# SPI_IFC.net
KiCad netlist of a schematic drawn in Altium Designer
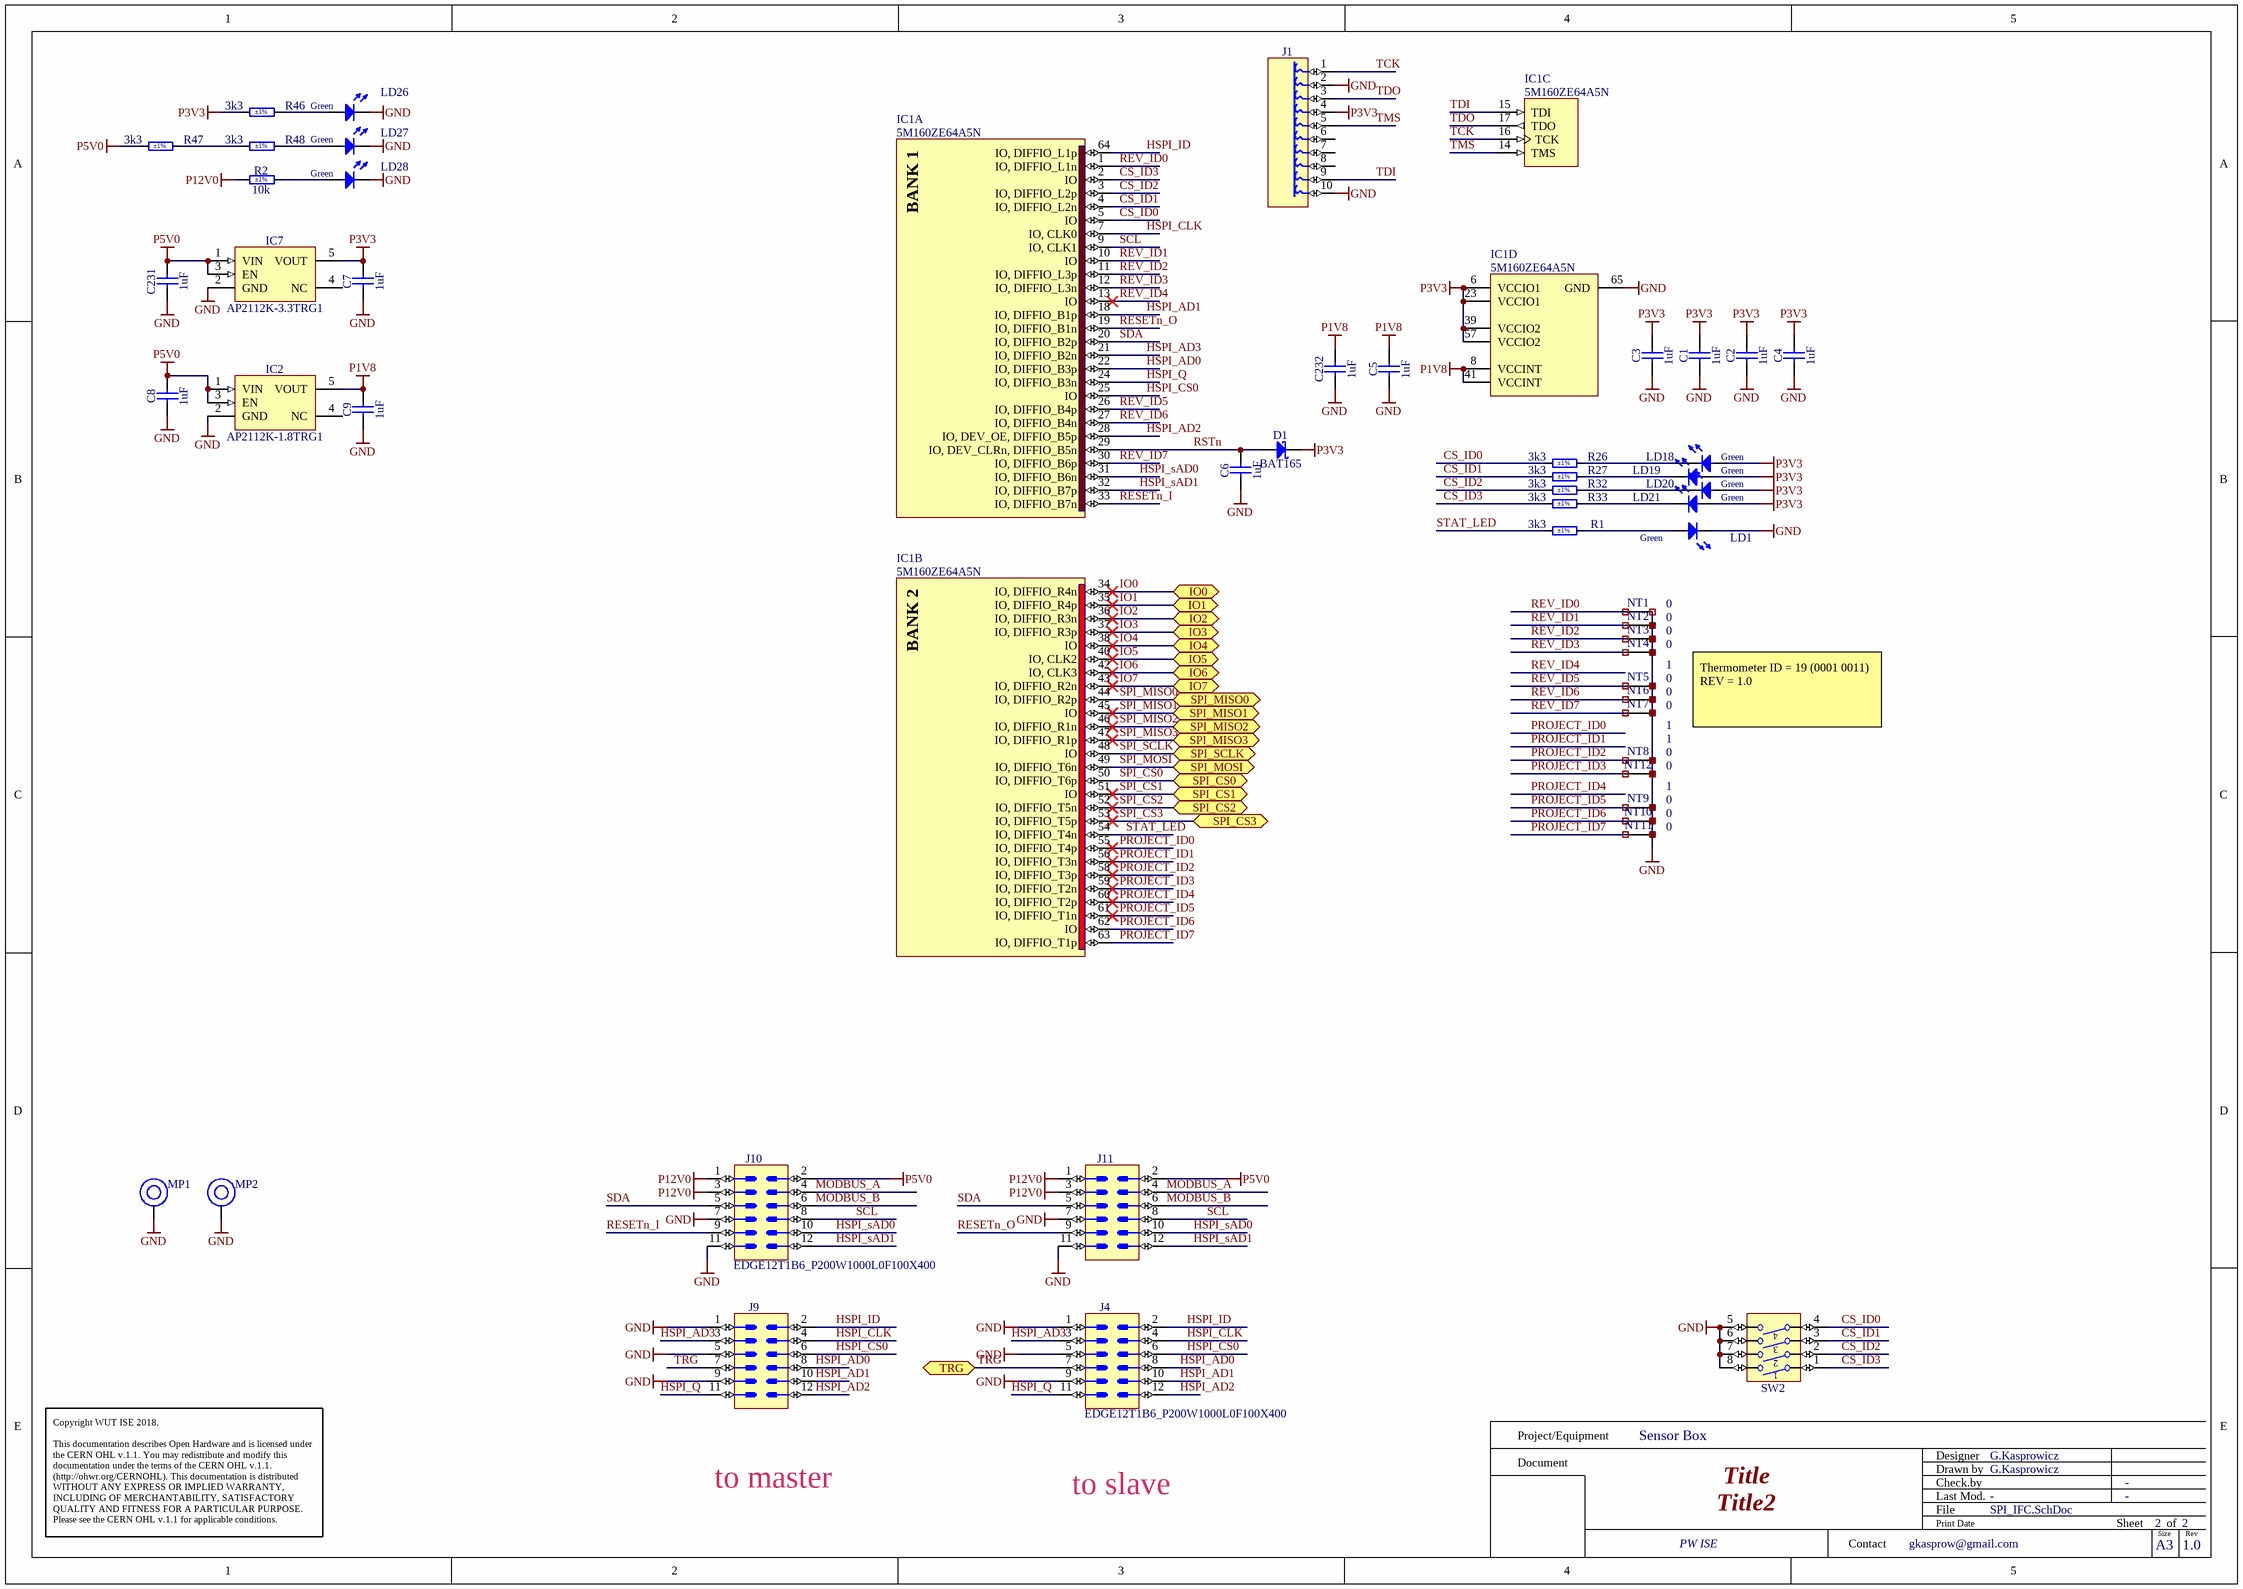
[diagram p0: SPI_IFC.SchDoc]

(export (version "E")
  (design (tool "Eeschema 10.0.6"))
  (components
    (comp (ref "C1")
      (value "1uF")
      (footprint "CAPC1005X55N")
      (description "Non-polarised capacitor")
      (fields
        (field (name "PART NUMBER") "CC0402_1UF_16V_10%_X5R")
        (field (name "VOLTAGE") "16V")
        (field (name "AUTHOR") "CERN DEM JLC")
      )
      (libsource (lib "Capacitors") (part "Capacitor - non polarized"))
    )
    (comp (ref "C2")
      (value "1uF")
      (footprint "CAPC1005X55N")
      (description "Non-polarised capacitor")
      (fields
        (field (name "PART NUMBER") "CC0402_1UF_16V_10%_X5R")
        (field (name "VOLTAGE") "16V")
        (field (name "AUTHOR") "CERN DEM JLC")
      )
      (libsource (lib "Capacitors") (part "Capacitor - non polarized"))
    )
    (comp (ref "C3")
      (value "1uF")
      (footprint "CAPC1005X55N")
      (description "Non-polarised capacitor")
      (fields
        (field (name "PART NUMBER") "CC0402_1UF_16V_10%_X5R")
        (field (name "VOLTAGE") "16V")
        (field (name "AUTHOR") "CERN DEM JLC")
      )
      (libsource (lib "Capacitors") (part "Capacitor - non polarized"))
    )
    (comp (ref "C4")
      (value "1uF")
      (footprint "CAPC1005X55N")
      (description "Non-polarised capacitor")
      (fields
        (field (name "PART NUMBER") "CC0402_1UF_16V_10%_X5R")
        (field (name "VOLTAGE") "16V")
        (field (name "AUTHOR") "CERN DEM JLC")
      )
      (libsource (lib "Capacitors") (part "Capacitor - non polarized"))
    )
    (comp (ref "C5")
      (value "1uF")
      (footprint "CAPC1005X55N")
      (description "Non-polarised capacitor")
      (fields
        (field (name "PART NUMBER") "CC0402_1UF_16V_10%_X5R")
        (field (name "VOLTAGE") "16V")
        (field (name "AUTHOR") "CERN DEM JLC")
      )
      (libsource (lib "Capacitors") (part "Capacitor - non polarized"))
    )
    (comp (ref "C6")
      (value "1uF")
      (footprint "CAPC1005X55N")
      (description "Non-polarised capacitor")
      (fields
        (field (name "PART NUMBER") "CC0402_1UF_16V_10%_X5R")
        (field (name "VOLTAGE") "16V")
        (field (name "AUTHOR") "CERN DEM JLC")
      )
      (libsource (lib "Capacitors") (part "Capacitor - non polarized"))
    )
    (comp (ref "C7")
      (value "1uF")
      (footprint "CAPC1005X55N")
      (description "Non-polarised capacitor")
      (fields
        (field (name "PART NUMBER") "CC0402_1UF_16V_10%_X5R")
        (field (name "VOLTAGE") "16V")
        (field (name "AUTHOR") "CERN DEM JLC")
      )
      (libsource (lib "Capacitors") (part "Capacitor - non polarized"))
    )
    (comp (ref "C8")
      (value "1uF")
      (footprint "CAPC1005X55N")
      (description "Non-polarised capacitor")
      (fields
        (field (name "PART NUMBER") "CC0402_1UF_16V_10%_X5R")
        (field (name "VOLTAGE") "16V")
        (field (name "AUTHOR") "CERN DEM JLC")
      )
      (libsource (lib "Capacitors") (part "Capacitor - non polarized"))
    )
    (comp (ref "C9")
      (value "1uF")
      (footprint "CAPC1005X55N")
      (description "Non-polarised capacitor")
      (fields
        (field (name "PART NUMBER") "CC0402_1UF_16V_10%_X5R")
        (field (name "VOLTAGE") "16V")
        (field (name "AUTHOR") "CERN DEM JLC")
      )
      (libsource (lib "Capacitors") (part "Capacitor - non polarized"))
    )
    (comp (ref "C231")
      (value "1uF")
      (footprint "CAPC1005X55N")
      (description "Non-polarised capacitor")
      (fields
        (field (name "PART NUMBER") "CC0402_1UF_16V_10%_X5R")
        (field (name "VOLTAGE") "16V")
        (field (name "AUTHOR") "CERN DEM JLC")
      )
      (libsource (lib "Capacitors") (part "Capacitor - non polarized"))
    )
    (comp (ref "C232")
      (value "1uF")
      (footprint "CAPC1005X55N")
      (description "Non-polarised capacitor")
      (fields
        (field (name "PART NUMBER") "CC0402_1UF_16V_10%_X5R")
        (field (name "VOLTAGE") "16V")
        (field (name "AUTHOR") "CERN DEM JLC")
      )
      (libsource (lib "Capacitors") (part "Capacitor - non polarized"))
    )
    (comp (ref "D1")
      (value "BAT165")
      (footprint "SOD2512X110N")
      (description "Schottky Diode")
      (fields
        (field (name "VOLTAGE") "40V")
        (field (name "POWER") "750mA")
        (field (name "AUTHOR") "CERN DEM JLC")
      )
      (libsource (lib "ICs And Semiconductors") (part "Diode Schottky"))
    )
    (comp (ref "IC1")
      (value "5M160ZE64A5N")
      (footprint "QFP40P900X900X120-65N-S550")
      (fields (field (name "MANUFACTURER") "ALTERA") (field (name "AUTHOR") "CERN DEM JLC"))
      (libsource (lib "ICs And Semiconductors") (part "5M160ZE64A5N"))
    )
    (comp (ref "IC2")
      (value "AP2112K-1.8TRG1")
      (footprint "SOT95P285X140-5N")
      (description "600mA CMOS Low Dropout Linear Regulator with Enable")
      (fields
        (field (name "MANUFACTURER") "DIODES INCORPORATED")
        (field (name "MANUFACTURER PART NUMBER") "AP2112K-1.8")
        (field (name "AUTHOR") "CERN DEM JLC")
      )
      (libsource (lib "ICs And Semiconductors") (part "AP2112K"))
    )
    (comp (ref "IC7")
      (value "AP2112K-3.3TRG1")
      (footprint "SOT95P285X140-5N")
      (description "600mA CMOS Low Dropout Linear Regulator with Enable")
      (fields
        (field (name "MANUFACTURER") "DIODES INCORPORATED")
        (field (name "MANUFACTURER PART NUMBER") "AP2112K-3.3")
        (field (name "AUTHOR") "CERN DEM MR")
      )
      (libsource (lib "ICs And Semiconductors") (part "AP2112K"))
    )
    (comp (ref "J1")
      (value "TC2050-IDC")
      (footprint "TC2050-IDC")
      (description "TC2030-MCP and TC2050-IDC Pad Contact")
      (fields (field (name "AUTHOR") "CERN DEM HF"))
      (libsource (lib "Eletro-mechanical") (part "TC2050-IDC"))
    )
    (comp (ref "J4")
      (value "~")
      (footprint "EDGE12T1B6_P200W1000L0F100X400")
      (description "PCB Edge Connector 12 (2x6)")
      (fields
        (field (name "PART NUMBER") "EDGE10T1B6_P200W1000L0F100X400")
        (field (name "AUTHOR") "CERN DEM MR")
      )
      (libsource (lib "Connectors") (part "PCB Edge Connector 12 (2x6)"))
    )
    (comp (ref "J9")
      (value "~")
      (footprint "EDGE12T5B10_P200W1000L0F100X400")
      (description "PCB Edge Connector 12 (2x6)")
      (fields (field (name "PART NUMBER") "EDGE12T5B10_P200W1000L0F100X400") (field (name "AUTHOR") "GK"))
      (libsource (lib "Connectors") (part "PCB Edge Connector 12 (2x6) R"))
    )
    (comp (ref "J10")
      (value "~")
      (footprint "EDGE12T1B6_P200W1000L0F100X400")
      (description "PCB Edge Connector 12 (2x6)")
      (fields
        (field (name "PART NUMBER") "EDGE10T1B6_P200W1000L0F100X400")
        (field (name "AUTHOR") "CERN DEM MR")
      )
      (libsource (lib "Connectors") (part "PCB Edge Connector 12 (2x6)"))
    )
    (comp (ref "J11")
      (value "~")
      (footprint "EDGE12T5B10_P200W1000L0F100X400")
      (description "PCB Edge Connector 12 (2x6)")
      (fields (field (name "PART NUMBER") "EDGE12T5B10_P200W1000L0F100X400") (field (name "AUTHOR") "GK"))
      (libsource (lib "Connectors") (part "PCB Edge Connector 12 (2x6) R"))
    )
    (comp (ref "LD1")
      (value "Green")
      (footprint "LED_KINGBRIGHT_KP-1608CGCK")
      (description "LED Green 1C 2A")
      (fields
        (field (name "PART NUMBER") "LED_KINGBRIGHT_KP-1608CGCK")
        (field (name "MANUFACTURER") "KINGBRIGHT")
        (field (name "AUTHOR") "CERN DEM HF")
      )
      (libsource (lib "ICs And Semiconductors") (part "LED Green 1C 2A"))
    )
    (comp (ref "LD18")
      (value "Green")
      (footprint "LED_KINGBRIGHT_KP-1608CGCK")
      (description "LED Green 1C 2A")
      (fields
        (field (name "PART NUMBER") "LED_KINGBRIGHT_KP-1608CGCK")
        (field (name "MANUFACTURER") "KINGBRIGHT")
        (field (name "AUTHOR") "CERN DEM HF")
      )
      (libsource (lib "ICs And Semiconductors") (part "LED Green 1C 2A"))
    )
    (comp (ref "LD19")
      (value "Green")
      (footprint "LED_KINGBRIGHT_KP-1608CGCK")
      (description "LED Green 1C 2A")
      (fields
        (field (name "PART NUMBER") "LED_KINGBRIGHT_KP-1608CGCK")
        (field (name "MANUFACTURER") "KINGBRIGHT")
        (field (name "AUTHOR") "CERN DEM HF")
      )
      (libsource (lib "ICs And Semiconductors") (part "LED Green 1C 2A"))
    )
    (comp (ref "LD20")
      (value "Green")
      (footprint "LED_KINGBRIGHT_KP-1608CGCK")
      (description "LED Green 1C 2A")
      (fields
        (field (name "PART NUMBER") "LED_KINGBRIGHT_KP-1608CGCK")
        (field (name "MANUFACTURER") "KINGBRIGHT")
        (field (name "AUTHOR") "CERN DEM HF")
      )
      (libsource (lib "ICs And Semiconductors") (part "LED Green 1C 2A"))
    )
    (comp (ref "LD21")
      (value "Green")
      (footprint "LED_KINGBRIGHT_KP-1608CGCK")
      (description "LED Green 1C 2A")
      (fields
        (field (name "PART NUMBER") "LED_KINGBRIGHT_KP-1608CGCK")
        (field (name "MANUFACTURER") "KINGBRIGHT")
        (field (name "AUTHOR") "CERN DEM HF")
      )
      (libsource (lib "ICs And Semiconductors") (part "LED Green 1C 2A"))
    )
    (comp (ref "LD26")
      (value "Green")
      (footprint "LED_KINGBRIGHT_KP-1608CGCK")
      (description "LED Green 1C 2A")
      (fields
        (field (name "PART NUMBER") "LED_KINGBRIGHT_KP-1608CGCK")
        (field (name "MANUFACTURER") "KINGBRIGHT")
        (field (name "AUTHOR") "CERN DEM HF")
      )
      (libsource (lib "ICs And Semiconductors") (part "LED Green 1C 2A"))
    )
    (comp (ref "LD27")
      (value "Green")
      (footprint "LED_KINGBRIGHT_KP-1608CGCK")
      (description "LED Green 1C 2A")
      (fields
        (field (name "PART NUMBER") "LED_KINGBRIGHT_KP-1608CGCK")
        (field (name "MANUFACTURER") "KINGBRIGHT")
        (field (name "AUTHOR") "CERN DEM HF")
      )
      (libsource (lib "ICs And Semiconductors") (part "LED Green 1C 2A"))
    )
    (comp (ref "LD28")
      (value "Green")
      (footprint "LED_KINGBRIGHT_KP-1608CGCK")
      (description "LED Green 1C 2A")
      (fields
        (field (name "PART NUMBER") "LED_KINGBRIGHT_KP-1608CGCK")
        (field (name "MANUFACTURER") "KINGBRIGHT")
        (field (name "AUTHOR") "CERN DEM HF")
      )
      (libsource (lib "ICs And Semiconductors") (part "LED Green 1C 2A"))
    )
    (comp (ref "MP1")
      (value "M1.6 x 3mm")
      (footprint "97730306330")
      (description "WA-SMSI SMT Steel Spacer with internal Thread Bottom closed, OD 3.3mm, M1.6 x 3mm")
      (fields
        (field (name "MANUFACTURER PART NUMBER") "97730306330R")
        (field (name "MANUFACTURER") "Wurth Elektronik")
      )
      (libsource (lib "Altium_WA-SMSI (rev22a)") (part "97730306330R"))
    )
    (comp (ref "MP2")
      (value "M1.6 x 3mm")
      (footprint "97730306330")
      (description "WA-SMSI SMT Steel Spacer with internal Thread Bottom closed, OD 3.3mm, M1.6 x 3mm")
      (fields
        (field (name "MANUFACTURER PART NUMBER") "97730306330R")
        (field (name "MANUFACTURER") "Wurth Elektronik")
      )
      (libsource (lib "Altium_WA-SMSI (rev22a)") (part "97730306330R"))
    )
    (comp (ref "NT1")
      (value "Net Tie")
      (footprint "Net Tie 3")
      (fields (field (name "PART NUMBER") "Net Tie 3") (field (name "AUTHOR") "CERN DEM HF"))
      (libsource (lib "Eletro-mechanical") (part "Net Tie_a"))
    )
    (comp (ref "NT2")
      (value "Net Tie")
      (footprint "Net Tie 3")
      (fields (field (name "PART NUMBER") "Net Tie 3") (field (name "AUTHOR") "CERN DEM HF"))
      (libsource (lib "Eletro-mechanical") (part "Net Tie_a"))
    )
    (comp (ref "NT3")
      (value "Net Tie")
      (footprint "Net Tie 3")
      (fields (field (name "PART NUMBER") "Net Tie 3") (field (name "AUTHOR") "CERN DEM HF"))
      (libsource (lib "Eletro-mechanical") (part "Net Tie_a"))
    )
    (comp (ref "NT4")
      (value "Net Tie")
      (footprint "Net Tie 3")
      (fields (field (name "PART NUMBER") "Net Tie 3") (field (name "AUTHOR") "CERN DEM HF"))
      (libsource (lib "Eletro-mechanical") (part "Net Tie_a"))
    )
    (comp (ref "NT5")
      (value "Net Tie")
      (footprint "Net Tie 3")
      (fields (field (name "PART NUMBER") "Net Tie 3") (field (name "AUTHOR") "CERN DEM HF"))
      (libsource (lib "Eletro-mechanical") (part "Net Tie_a"))
    )
    (comp (ref "NT6")
      (value "Net Tie")
      (footprint "Net Tie 3")
      (fields (field (name "PART NUMBER") "Net Tie 3") (field (name "AUTHOR") "CERN DEM HF"))
      (libsource (lib "Eletro-mechanical") (part "Net Tie_a"))
    )
    (comp (ref "NT7")
      (value "Net Tie")
      (footprint "Net Tie 3")
      (fields (field (name "PART NUMBER") "Net Tie 3") (field (name "AUTHOR") "CERN DEM HF"))
      (libsource (lib "Eletro-mechanical") (part "Net Tie_a"))
    )
    (comp (ref "NT8")
      (value "Net Tie")
      (footprint "Net Tie 3")
      (fields (field (name "PART NUMBER") "Net Tie 3") (field (name "AUTHOR") "CERN DEM HF"))
      (libsource (lib "Eletro-mechanical") (part "Net Tie_a"))
    )
    (comp (ref "NT9")
      (value "Net Tie")
      (footprint "Net Tie 3")
      (fields (field (name "PART NUMBER") "Net Tie 3") (field (name "AUTHOR") "CERN DEM HF"))
      (libsource (lib "Eletro-mechanical") (part "Net Tie_a"))
    )
    (comp (ref "NT10")
      (value "Net Tie")
      (footprint "Net Tie 3")
      (fields (field (name "PART NUMBER") "Net Tie 3") (field (name "AUTHOR") "CERN DEM HF"))
      (libsource (lib "Eletro-mechanical") (part "Net Tie_a"))
    )
    (comp (ref "NT11")
      (value "Net Tie")
      (footprint "Net Tie 3")
      (fields (field (name "PART NUMBER") "Net Tie 3") (field (name "AUTHOR") "CERN DEM HF"))
      (libsource (lib "Eletro-mechanical") (part "Net Tie_a"))
    )
    (comp (ref "NT12")
      (value "Net Tie")
      (footprint "Net Tie 3")
      (fields (field (name "PART NUMBER") "Net Tie 3") (field (name "AUTHOR") "CERN DEM HF"))
      (libsource (lib "Eletro-mechanical") (part "Net Tie_a"))
    )
    (comp (ref "R1")
      (value "3k3")
      (footprint "RESC1005X40N")
      (description "Resistor - 1%")
      (fields
        (field (name "TOLERANCE") "±1%")
        (field (name "PART NUMBER") "R0402_3K3_1%_0.0625W_100PPM")
        (field (name "POWER") "0.0625W")
        (field (name "AUTHOR") "CERN DEM JLC")
      )
      (libsource (lib "Resistors") (part "Resistor - 1%"))
    )
    (comp (ref "R2")
      (value "10k")
      (footprint "RESC1005X40N")
      (description "Resistor - 1%")
      (fields
        (field (name "TOLERANCE") "±1%")
        (field (name "PART NUMBER") "R0402_10K_1%_0.0625W_100PPM")
        (field (name "POWER") "0.0625W")
        (field (name "AUTHOR") "CERN DEM JLC")
      )
      (libsource (lib "Resistors") (part "Resistor - 1%"))
    )
    (comp (ref "R26")
      (value "3k3")
      (footprint "RESC1005X40N")
      (description "Resistor - 1%")
      (fields
        (field (name "TOLERANCE") "±1%")
        (field (name "PART NUMBER") "R0402_3K3_1%_0.0625W_100PPM")
        (field (name "POWER") "0.0625W")
        (field (name "AUTHOR") "CERN DEM JLC")
      )
      (libsource (lib "Resistors") (part "Resistor - 1%"))
    )
    (comp (ref "R27")
      (value "3k3")
      (footprint "RESC1005X40N")
      (description "Resistor - 1%")
      (fields
        (field (name "TOLERANCE") "±1%")
        (field (name "PART NUMBER") "R0402_3K3_1%_0.0625W_100PPM")
        (field (name "POWER") "0.0625W")
        (field (name "AUTHOR") "CERN DEM JLC")
      )
      (libsource (lib "Resistors") (part "Resistor - 1%"))
    )
    (comp (ref "R32")
      (value "3k3")
      (footprint "RESC1005X40N")
      (description "Resistor - 1%")
      (fields
        (field (name "TOLERANCE") "±1%")
        (field (name "PART NUMBER") "R0402_3K3_1%_0.0625W_100PPM")
        (field (name "POWER") "0.0625W")
        (field (name "AUTHOR") "CERN DEM JLC")
      )
      (libsource (lib "Resistors") (part "Resistor - 1%"))
    )
    (comp (ref "R33")
      (value "3k3")
      (footprint "RESC1005X40N")
      (description "Resistor - 1%")
      (fields
        (field (name "TOLERANCE") "±1%")
        (field (name "PART NUMBER") "R0402_3K3_1%_0.0625W_100PPM")
        (field (name "POWER") "0.0625W")
        (field (name "AUTHOR") "CERN DEM JLC")
      )
      (libsource (lib "Resistors") (part "Resistor - 1%"))
    )
    (comp (ref "R46")
      (value "3k3")
      (footprint "RESC1005X40N")
      (description "Resistor - 1%")
      (fields
        (field (name "TOLERANCE") "±1%")
        (field (name "PART NUMBER") "R0402_3K3_1%_0.0625W_100PPM")
        (field (name "POWER") "0.0625W")
        (field (name "AUTHOR") "CERN DEM JLC")
      )
      (libsource (lib "Resistors") (part "Resistor - 1%"))
    )
    (comp (ref "R47")
      (value "3k3")
      (footprint "RESC1005X40N")
      (description "Resistor - 1%")
      (fields
        (field (name "TOLERANCE") "±1%")
        (field (name "PART NUMBER") "R0402_3K3_1%_0.0625W_100PPM")
        (field (name "POWER") "0.0625W")
        (field (name "AUTHOR") "CERN DEM JLC")
      )
      (libsource (lib "Resistors") (part "Resistor - 1%"))
    )
    (comp (ref "R48")
      (value "3k3")
      (footprint "RESC1005X40N")
      (description "Resistor - 1%")
      (fields
        (field (name "TOLERANCE") "±1%")
        (field (name "PART NUMBER") "R0402_3K3_1%_0.0625W_100PPM")
        (field (name "POWER") "0.0625W")
        (field (name "AUTHOR") "CERN DEM JLC")
      )
      (libsource (lib "Resistors") (part "Resistor - 1%"))
    )
    (comp (ref "SW2")
      (value "Switch")
      (footprint "SW_OMRON_A6H-4102")
      (description "4 Ways SPST DIP Switch")
      (fields
        (field (name "PART NUMBER") "SW_OMRON_A6H-4102")
        (field (name "MANUFACTURER") "OMRON")
        (field (name "AUTHOR") "CERN DEM JLC")
      )
      (libsource (lib "Eletro-mechanical") (part "SW 4x SPST DIP Switch"))
    )
  )
  (nets
    (net (code "1") (name "/CS_ID0") (class "Default")
      (node (ref "IC1") (pin "5") (pinfunction "IO_5") (pintype "bidirectional"))
      (node (ref "R26") (pin "2") (pinfunction "2_2") (pintype "passive"))
      (node (ref "SW2") (pin "4") (pinfunction "4_4") (pintype "bidirectional"))
    )
    (net (code "2") (name "/CS_ID1") (class "Default")
      (node (ref "IC1") (pin "4") (pinfunction "IO,_DIFFIO_L2n_4") (pintype "bidirectional"))
      (node (ref "R27") (pin "2") (pinfunction "2_2") (pintype "passive"))
      (node (ref "SW2") (pin "3") (pinfunction "3_3") (pintype "bidirectional"))
    )
    (net (code "3") (name "/CS_ID2") (class "Default")
      (node (ref "IC1") (pin "3") (pinfunction "IO,_DIFFIO_L2p_3") (pintype "bidirectional"))
      (node (ref "R32") (pin "2") (pinfunction "2_2") (pintype "passive"))
      (node (ref "SW2") (pin "2") (pinfunction "2_2") (pintype "bidirectional"))
    )
    (net (code "4") (name "/CS_ID3") (class "Default")
      (node (ref "IC1") (pin "2") (pinfunction "IO_2") (pintype "bidirectional"))
      (node (ref "R33") (pin "2") (pinfunction "2_2") (pintype "passive"))
      (node (ref "SW2") (pin "1") (pinfunction "1_1") (pintype "bidirectional"))
    )
    (net (code "5") (name "/HSPI_AD0") (class "Default")
      (node (ref "IC1") (pin "22") (pinfunction "IO,_DIFFIO_B3p_22") (pintype "bidirectional"))
      (node (ref "J4") (pin "8") (pinfunction "8_8") (pintype "bidirectional"))
      (node (ref "J9") (pin "8") (pinfunction "8_8") (pintype "bidirectional"))
    )
    (net (code "6") (name "/HSPI_AD1") (class "Default")
      (node (ref "IC1") (pin "18") (pinfunction "IO,_DIFFIO_B1p_18") (pintype "bidirectional"))
      (node (ref "J4") (pin "10") (pinfunction "10_10") (pintype "bidirectional"))
      (node (ref "J9") (pin "10") (pinfunction "10_10") (pintype "bidirectional"))
    )
    (net (code "7") (name "/HSPI_AD2") (class "Default")
      (node (ref "IC1") (pin "28") (pinfunction "IO,_DEV_OE,_DIFFIO_B5p_28") (pintype "bidirectional"))
      (node (ref "J4") (pin "12") (pinfunction "12_12") (pintype "bidirectional"))
      (node (ref "J9") (pin "12") (pinfunction "12_12") (pintype "bidirectional"))
    )
    (net (code "8") (name "/HSPI_AD3") (class "Default")
      (node (ref "IC1") (pin "21") (pinfunction "IO,_DIFFIO_B2n_21") (pintype "bidirectional"))
      (node (ref "J4") (pin "3") (pinfunction "3_3") (pintype "bidirectional"))
      (node (ref "J9") (pin "3") (pinfunction "3_3") (pintype "bidirectional"))
    )
    (net (code "9") (name "/HSPI_CLK") (class "Default")
      (node (ref "IC1") (pin "7") (pinfunction "IO,_CLK0_7") (pintype "bidirectional"))
      (node (ref "J4") (pin "4") (pinfunction "4_4") (pintype "bidirectional"))
      (node (ref "J9") (pin "4") (pinfunction "4_4") (pintype "bidirectional"))
    )
    (net (code "10") (name "/HSPI_CS0") (class "Default")
      (node (ref "IC1") (pin "25") (pinfunction "IO_25") (pintype "bidirectional"))
      (node (ref "J4") (pin "6") (pinfunction "6_6") (pintype "bidirectional"))
      (node (ref "J9") (pin "6") (pinfunction "6_6") (pintype "bidirectional"))
    )
    (net (code "11") (name "/HSPI_ID") (class "Default")
      (node (ref "IC1") (pin "64") (pinfunction "IO,_DIFFIO_L1p_64") (pintype "bidirectional"))
      (node (ref "J4") (pin "2") (pinfunction "2_2") (pintype "bidirectional"))
      (node (ref "J9") (pin "2") (pinfunction "2_2") (pintype "bidirectional"))
    )
    (net (code "12") (name "/HSPI_Q") (class "Default")
      (node (ref "IC1") (pin "24") (pinfunction "IO,_DIFFIO_B3n_24") (pintype "bidirectional"))
      (node (ref "J4") (pin "11") (pinfunction "11_11") (pintype "bidirectional"))
      (node (ref "J9") (pin "11") (pinfunction "11_11") (pintype "bidirectional"))
    )
    (net (code "13") (name "/HSPI_sAD0") (class "Default")
      (node (ref "IC1") (pin "31") (pinfunction "IO,_DIFFIO_B6n_31") (pintype "bidirectional"))
      (node (ref "J10") (pin "10") (pinfunction "10_10") (pintype "bidirectional"))
      (node (ref "J11") (pin "10") (pinfunction "10_10") (pintype "bidirectional"))
    )
    (net (code "14") (name "/HSPI_sAD1") (class "Default")
      (node (ref "IC1") (pin "32") (pinfunction "IO,_DIFFIO_B7p_32") (pintype "bidirectional"))
      (node (ref "J10") (pin "12") (pinfunction "12_12") (pintype "bidirectional"))
      (node (ref "J11") (pin "12") (pinfunction "12_12") (pintype "bidirectional"))
    )
    (net (code "15") (name "/IO0") (class "Default")
      (node (ref "IC1") (pin "34") (pinfunction "IO,_DIFFIO_R4n_34") (pintype "bidirectional+no_connect"))
    )
    (net (code "16") (name "/IO1") (class "Default")
      (node (ref "IC1") (pin "35") (pinfunction "IO,_DIFFIO_R4p_35") (pintype "bidirectional+no_connect"))
    )
    (net (code "17") (name "/IO2") (class "Default")
      (node (ref "IC1") (pin "36") (pinfunction "IO,_DIFFIO_R3n_36") (pintype "bidirectional+no_connect"))
    )
    (net (code "18") (name "/IO3") (class "Default")
      (node (ref "IC1") (pin "37") (pinfunction "IO,_DIFFIO_R3p_37") (pintype "bidirectional+no_connect"))
    )
    (net (code "19") (name "/IO4") (class "Default")
      (node (ref "IC1") (pin "38") (pinfunction "IO_38") (pintype "bidirectional+no_connect"))
    )
    (net (code "20") (name "/IO5") (class "Default")
      (node (ref "IC1") (pin "40") (pinfunction "IO,_CLK2_40") (pintype "bidirectional+no_connect"))
    )
    (net (code "21") (name "/IO6") (class "Default")
      (node (ref "IC1") (pin "42") (pinfunction "IO,_CLK3_42") (pintype "bidirectional+no_connect"))
    )
    (net (code "22") (name "/IO7") (class "Default")
      (node (ref "IC1") (pin "43") (pinfunction "IO,_DIFFIO_R2n_43") (pintype "bidirectional+no_connect"))
    )
    (net (code "23") (name "/MODBUS_A") (class "Default")
      (node (ref "J10") (pin "4") (pinfunction "4_4") (pintype "bidirectional"))
      (node (ref "J11") (pin "4") (pinfunction "4_4") (pintype "bidirectional"))
    )
    (net (code "24") (name "/MODBUS_B") (class "Default")
      (node (ref "J10") (pin "6") (pinfunction "6_6") (pintype "bidirectional"))
      (node (ref "J11") (pin "6") (pinfunction "6_6") (pintype "bidirectional"))
    )
    (net (code "25") (name "/PROJECT_ID0") (class "Default")
      (node (ref "IC1") (pin "55") (pinfunction "IO,_DIFFIO_T4p_55") (pintype "bidirectional"))
    )
    (net (code "26") (name "/PROJECT_ID1") (class "Default")
      (node (ref "IC1") (pin "56") (pinfunction "IO,_DIFFIO_T3n_56") (pintype "bidirectional"))
    )
    (net (code "27") (name "/PROJECT_ID2") (class "Default")
      (node (ref "IC1") (pin "58") (pinfunction "IO,_DIFFIO_T3p_58") (pintype "bidirectional"))
      (node (ref "NT8") (pin "1") (pinfunction "1_1") (pintype "bidirectional"))
    )
    (net (code "28") (name "/PROJECT_ID3") (class "Default")
      (node (ref "IC1") (pin "59") (pinfunction "IO,_DIFFIO_T2n_59") (pintype "bidirectional"))
      (node (ref "NT12") (pin "1") (pinfunction "1_1") (pintype "bidirectional"))
    )
    (net (code "29") (name "/PROJECT_ID4") (class "Default")
      (node (ref "IC1") (pin "60") (pinfunction "IO,_DIFFIO_T2p_60") (pintype "bidirectional"))
    )
    (net (code "30") (name "/PROJECT_ID5") (class "Default")
      (node (ref "IC1") (pin "61") (pinfunction "IO,_DIFFIO_T1n_61") (pintype "bidirectional"))
      (node (ref "NT9") (pin "1") (pinfunction "1_1") (pintype "bidirectional"))
    )
    (net (code "31") (name "/PROJECT_ID6") (class "Default")
      (node (ref "IC1") (pin "62") (pinfunction "IO_62") (pintype "bidirectional"))
      (node (ref "NT10") (pin "1") (pinfunction "1_1") (pintype "bidirectional"))
    )
    (net (code "32") (name "/PROJECT_ID7") (class "Default")
      (node (ref "IC1") (pin "63") (pinfunction "IO,_DIFFIO_T1p_63") (pintype "bidirectional"))
      (node (ref "NT11") (pin "1") (pinfunction "1_1") (pintype "bidirectional"))
    )
    (net (code "33") (name "/RESETn_I") (class "Default")
      (node (ref "IC1") (pin "33") (pinfunction "IO,_DIFFIO_B7n_33") (pintype "bidirectional"))
      (node (ref "J10") (pin "9") (pinfunction "9_9") (pintype "bidirectional"))
    )
    (net (code "34") (name "/RESETn_O") (class "Default")
      (node (ref "IC1") (pin "19") (pinfunction "IO,_DIFFIO_B1n_19") (pintype "bidirectional"))
      (node (ref "J11") (pin "9") (pinfunction "9_9") (pintype "bidirectional"))
    )
    (net (code "35") (name "/REV_ID0") (class "Default")
      (node (ref "IC1") (pin "1") (pinfunction "IO,_DIFFIO_L1n_1") (pintype "bidirectional"))
      (node (ref "NT1") (pin "1") (pinfunction "1_1") (pintype "bidirectional"))
    )
    (net (code "36") (name "/REV_ID1") (class "Default")
      (node (ref "IC1") (pin "10") (pinfunction "IO_10") (pintype "bidirectional"))
      (node (ref "NT2") (pin "1") (pinfunction "1_1") (pintype "bidirectional"))
    )
    (net (code "37") (name "/REV_ID2") (class "Default")
      (node (ref "IC1") (pin "11") (pinfunction "IO,_DIFFIO_L3p_11") (pintype "bidirectional"))
      (node (ref "NT3") (pin "1") (pinfunction "1_1") (pintype "bidirectional"))
    )
    (net (code "38") (name "/REV_ID3") (class "Default")
      (node (ref "IC1") (pin "12") (pinfunction "IO,_DIFFIO_L3n_12") (pintype "bidirectional"))
      (node (ref "NT4") (pin "1") (pinfunction "1_1") (pintype "bidirectional"))
    )
    (net (code "39") (name "/REV_ID4") (class "Default")
      (node (ref "IC1") (pin "13") (pinfunction "IO_13") (pintype "bidirectional+no_connect"))
    )
    (net (code "40") (name "/REV_ID5") (class "Default")
      (node (ref "IC1") (pin "26") (pinfunction "IO,_DIFFIO_B4p_26") (pintype "bidirectional"))
      (node (ref "NT5") (pin "1") (pinfunction "1_1") (pintype "bidirectional"))
    )
    (net (code "41") (name "/REV_ID6") (class "Default")
      (node (ref "IC1") (pin "27") (pinfunction "IO,_DIFFIO_B4n_27") (pintype "bidirectional"))
      (node (ref "NT6") (pin "1") (pinfunction "1_1") (pintype "bidirectional"))
    )
    (net (code "42") (name "/REV_ID7") (class "Default")
      (node (ref "IC1") (pin "30") (pinfunction "IO,_DIFFIO_B6p_30") (pintype "bidirectional"))
      (node (ref "NT7") (pin "1") (pinfunction "1_1") (pintype "bidirectional"))
    )
    (net (code "43") (name "/RSTn") (class "Default")
      (node (ref "C6") (pin "2") (pinfunction "2_2") (pintype "passive"))
      (node (ref "D1") (pin "2") (pinfunction "A_2") (pintype "passive"))
      (node (ref "IC1") (pin "29") (pinfunction "IO,_DEV_CLRn,_DIFFIO_B5n_29") (pintype "bidirectional"))
    )
    (net (code "44") (name "/SCL") (class "Default")
      (node (ref "IC1") (pin "9") (pinfunction "IO,_CLK1_9") (pintype "bidirectional"))
      (node (ref "J10") (pin "8") (pinfunction "8_8") (pintype "bidirectional"))
      (node (ref "J11") (pin "8") (pinfunction "8_8") (pintype "bidirectional"))
    )
    (net (code "45") (name "/SDA") (class "Default")
      (node (ref "IC1") (pin "20") (pinfunction "IO,_DIFFIO_B2p_20") (pintype "bidirectional"))
      (node (ref "J10") (pin "5") (pinfunction "5_5") (pintype "bidirectional"))
      (node (ref "J11") (pin "5") (pinfunction "5_5") (pintype "bidirectional"))
    )
    (net (code "46") (name "/SPI_CS0") (class "Default")
      (node (ref "IC1") (pin "50") (pinfunction "IO,_DIFFIO_T6p_50") (pintype "bidirectional"))
    )
    (net (code "47") (name "/SPI_CS1") (class "Default")
      (node (ref "IC1") (pin "51") (pinfunction "IO_51") (pintype "bidirectional+no_connect"))
    )
    (net (code "48") (name "/SPI_CS2") (class "Default")
      (node (ref "IC1") (pin "52") (pinfunction "IO,_DIFFIO_T5n_52") (pintype "bidirectional+no_connect"))
    )
    (net (code "49") (name "/SPI_CS3") (class "Default")
      (node (ref "IC1") (pin "53") (pinfunction "IO,_DIFFIO_T5p_53") (pintype "bidirectional+no_connect"))
    )
    (net (code "50") (name "/SPI_MISO0") (class "Default")
      (node (ref "IC1") (pin "44") (pinfunction "IO,_DIFFIO_R2p_44") (pintype "bidirectional"))
    )
    (net (code "51") (name "/SPI_MISO1") (class "Default")
      (node (ref "IC1") (pin "45") (pinfunction "IO_45") (pintype "bidirectional+no_connect"))
    )
    (net (code "52") (name "/SPI_MISO2") (class "Default")
      (node (ref "IC1") (pin "46") (pinfunction "IO,_DIFFIO_R1n_46") (pintype "bidirectional+no_connect"))
    )
    (net (code "53") (name "/SPI_MISO3") (class "Default")
      (node (ref "IC1") (pin "47") (pinfunction "IO,_DIFFIO_R1p_47") (pintype "bidirectional+no_connect"))
    )
    (net (code "54") (name "/SPI_MOSI") (class "Default")
      (node (ref "IC1") (pin "49") (pinfunction "IO,_DIFFIO_T6n_49") (pintype "bidirectional"))
    )
    (net (code "55") (name "/SPI_SCLK") (class "Default")
      (node (ref "IC1") (pin "48") (pinfunction "IO_48") (pintype "bidirectional"))
    )
    (net (code "56") (name "/STAT_LED") (class "Default")
      (node (ref "IC1") (pin "54") (pinfunction "IO,_DIFFIO_T4n_54") (pintype "bidirectional"))
      (node (ref "R1") (pin "2") (pinfunction "2_2") (pintype "passive"))
    )
    (net (code "57") (name "/TCK") (class "Default")
      (node (ref "IC1") (pin "16") (pinfunction "TCK_16") (pintype "input"))
      (node (ref "J1") (pin "1") (pinfunction "1_1") (pintype "bidirectional"))
    )
    (net (code "58") (name "/TDI") (class "Default")
      (node (ref "IC1") (pin "15") (pinfunction "TDI_15") (pintype "input"))
      (node (ref "J1") (pin "9") (pinfunction "9_9") (pintype "bidirectional"))
    )
    (net (code "59") (name "/TDO") (class "Default")
      (node (ref "IC1") (pin "17") (pinfunction "TDO_17") (pintype "output"))
      (node (ref "J1") (pin "3") (pinfunction "3_3") (pintype "bidirectional"))
    )
    (net (code "60") (name "/TMS") (class "Default")
      (node (ref "IC1") (pin "14") (pinfunction "TMS_14") (pintype "input"))
      (node (ref "J1") (pin "5") (pinfunction "5_5") (pintype "bidirectional"))
    )
    (net (code "61") (name "/TRG") (class "Default")
      (node (ref "J4") (pin "7") (pinfunction "7_7") (pintype "bidirectional"))
      (node (ref "J9") (pin "7") (pinfunction "7_7") (pintype "bidirectional"))
    )
    (net (code "62") (name "GND") (class "Default")
      (node (ref "C1") (pin "1") (pinfunction "1_1") (pintype "passive"))
      (node (ref "C2") (pin "1") (pinfunction "1_1") (pintype "passive"))
      (node (ref "C231") (pin "1") (pinfunction "1_1") (pintype "passive"))
      (node (ref "C232") (pin "1") (pinfunction "1_1") (pintype "passive"))
      (node (ref "C3") (pin "1") (pinfunction "1_1") (pintype "passive"))
      (node (ref "C4") (pin "1") (pinfunction "1_1") (pintype "passive"))
      (node (ref "C5") (pin "1") (pinfunction "1_1") (pintype "passive"))
      (node (ref "C6") (pin "1") (pinfunction "1_1") (pintype "passive"))
      (node (ref "C7") (pin "1") (pinfunction "1_1") (pintype "passive"))
      (node (ref "C8") (pin "1") (pinfunction "1_1") (pintype "passive"))
      (node (ref "C9") (pin "1") (pinfunction "1_1") (pintype "passive"))
      (node (ref "IC1") (pin "65") (pinfunction "GND_65") (pintype "power_in"))
      (node (ref "IC2") (pin "2") (pinfunction "GND_2") (pintype "power_in"))
      (node (ref "IC7") (pin "2") (pinfunction "GND_2") (pintype "power_in"))
      (node (ref "J1") (pin "10") (pinfunction "10_10") (pintype "bidirectional"))
      (node (ref "J1") (pin "2") (pinfunction "2_2") (pintype "bidirectional"))
      (node (ref "J10") (pin "11") (pinfunction "11_11") (pintype "bidirectional"))
      (node (ref "J10") (pin "7") (pinfunction "7_7") (pintype "bidirectional"))
      (node (ref "J11") (pin "11") (pinfunction "11_11") (pintype "bidirectional"))
      (node (ref "J11") (pin "7") (pinfunction "7_7") (pintype "bidirectional"))
      (node (ref "J4") (pin "1") (pinfunction "1_1") (pintype "bidirectional"))
      (node (ref "J4") (pin "5") (pinfunction "5_5") (pintype "bidirectional"))
      (node (ref "J4") (pin "9") (pinfunction "9_9") (pintype "bidirectional"))
      (node (ref "J9") (pin "1") (pinfunction "1_1") (pintype "bidirectional"))
      (node (ref "J9") (pin "5") (pinfunction "5_5") (pintype "bidirectional"))
      (node (ref "J9") (pin "9") (pinfunction "9_9") (pintype "bidirectional"))
      (node (ref "LD1") (pin "1") (pinfunction "C_1") (pintype "passive"))
      (node (ref "LD26") (pin "1") (pinfunction "C_1") (pintype "passive"))
      (node (ref "LD27") (pin "1") (pinfunction "C_1") (pintype "passive"))
      (node (ref "LD28") (pin "1") (pinfunction "C_1") (pintype "passive"))
      (node (ref "MP1") (pin "1") (pinfunction "1_1") (pintype "passive"))
      (node (ref "MP2") (pin "1") (pinfunction "1_1") (pintype "passive"))
      (node (ref "NT1") (pin "2") (pinfunction "2_2") (pintype "bidirectional"))
      (node (ref "NT10") (pin "2") (pinfunction "2_2") (pintype "bidirectional"))
      (node (ref "NT11") (pin "2") (pinfunction "2_2") (pintype "bidirectional"))
      (node (ref "NT12") (pin "2") (pinfunction "2_2") (pintype "bidirectional"))
      (node (ref "NT2") (pin "2") (pinfunction "2_2") (pintype "bidirectional"))
      (node (ref "NT3") (pin "2") (pinfunction "2_2") (pintype "bidirectional"))
      (node (ref "NT4") (pin "2") (pinfunction "2_2") (pintype "bidirectional"))
      (node (ref "NT5") (pin "2") (pinfunction "2_2") (pintype "bidirectional"))
      (node (ref "NT6") (pin "2") (pinfunction "2_2") (pintype "bidirectional"))
      (node (ref "NT7") (pin "2") (pinfunction "2_2") (pintype "bidirectional"))
      (node (ref "NT8") (pin "2") (pinfunction "2_2") (pintype "bidirectional"))
      (node (ref "NT9") (pin "2") (pinfunction "2_2") (pintype "bidirectional"))
      (node (ref "SW2") (pin "5") (pinfunction "5_5") (pintype "bidirectional"))
      (node (ref "SW2") (pin "6") (pinfunction "6_6") (pintype "bidirectional"))
      (node (ref "SW2") (pin "7") (pinfunction "7_7") (pintype "bidirectional"))
      (node (ref "SW2") (pin "8") (pinfunction "8_8") (pintype "bidirectional"))
    )
    (net (code "63") (name "Net-(LD1-A)") (class "Default")
      (node (ref "LD1") (pin "2") (pinfunction "A_2") (pintype "passive"))
      (node (ref "R1") (pin "1") (pinfunction "1_1") (pintype "passive"))
    )
    (net (code "64") (name "Net-(LD18-C)") (class "Default")
      (node (ref "LD18") (pin "1") (pinfunction "C_1") (pintype "passive"))
      (node (ref "R26") (pin "1") (pinfunction "1_1") (pintype "passive"))
    )
    (net (code "65") (name "Net-(LD19-C)") (class "Default")
      (node (ref "LD19") (pin "1") (pinfunction "C_1") (pintype "passive"))
      (node (ref "R27") (pin "1") (pinfunction "1_1") (pintype "passive"))
    )
    (net (code "66") (name "Net-(LD20-C)") (class "Default")
      (node (ref "LD20") (pin "1") (pinfunction "C_1") (pintype "passive"))
      (node (ref "R32") (pin "1") (pinfunction "1_1") (pintype "passive"))
    )
    (net (code "67") (name "Net-(LD21-C)") (class "Default")
      (node (ref "LD21") (pin "1") (pinfunction "C_1") (pintype "passive"))
      (node (ref "R33") (pin "1") (pinfunction "1_1") (pintype "passive"))
    )
    (net (code "68") (name "Net-(LD26-A)") (class "Default")
      (node (ref "LD26") (pin "2") (pinfunction "A_2") (pintype "passive"))
      (node (ref "R46") (pin "1") (pinfunction "1_1") (pintype "passive"))
    )
    (net (code "69") (name "Net-(LD27-A)") (class "Default")
      (node (ref "LD27") (pin "2") (pinfunction "A_2") (pintype "passive"))
      (node (ref "R48") (pin "1") (pinfunction "1_1") (pintype "passive"))
    )
    (net (code "70") (name "Net-(LD28-A)") (class "Default")
      (node (ref "LD28") (pin "2") (pinfunction "A_2") (pintype "passive"))
      (node (ref "R2") (pin "2") (pinfunction "2_2") (pintype "passive"))
    )
    (net (code "71") (name "Net-(R47-Pad1)") (class "Default")
      (node (ref "R47") (pin "1") (pinfunction "1_1") (pintype "passive"))
      (node (ref "R48") (pin "2") (pinfunction "2_2") (pintype "passive"))
    )
    (net (code "72") (name "P1V8") (class "Default")
      (node (ref "C232") (pin "2") (pinfunction "2_2") (pintype "passive"))
      (node (ref "C5") (pin "2") (pinfunction "2_2") (pintype "passive"))
      (node (ref "C9") (pin "2") (pinfunction "2_2") (pintype "passive"))
      (node (ref "IC1") (pin "41") (pinfunction "VCCINT_41") (pintype "power_in"))
      (node (ref "IC1") (pin "8") (pinfunction "VCCINT_8") (pintype "power_in"))
      (node (ref "IC2") (pin "5") (pinfunction "VOUT_5") (pintype "power_in"))
    )
    (net (code "73") (name "P3V3") (class "Default")
      (node (ref "C1") (pin "2") (pinfunction "2_2") (pintype "passive"))
      (node (ref "C2") (pin "2") (pinfunction "2_2") (pintype "passive"))
      (node (ref "C3") (pin "2") (pinfunction "2_2") (pintype "passive"))
      (node (ref "C4") (pin "2") (pinfunction "2_2") (pintype "passive"))
      (node (ref "C7") (pin "2") (pinfunction "2_2") (pintype "passive"))
      (node (ref "D1") (pin "1") (pinfunction "C_1") (pintype "passive"))
      (node (ref "IC1") (pin "23") (pinfunction "VCCIO1_23") (pintype "power_in"))
      (node (ref "IC1") (pin "39") (pinfunction "VCCIO2_39") (pintype "power_in"))
      (node (ref "IC1") (pin "57") (pinfunction "VCCIO2_57") (pintype "power_in"))
      (node (ref "IC1") (pin "6") (pinfunction "VCCIO1_6") (pintype "power_in"))
      (node (ref "IC7") (pin "5") (pinfunction "VOUT_5") (pintype "power_in"))
      (node (ref "J1") (pin "4") (pinfunction "4_4") (pintype "bidirectional"))
      (node (ref "LD18") (pin "2") (pinfunction "A_2") (pintype "passive"))
      (node (ref "LD19") (pin "2") (pinfunction "A_2") (pintype "passive"))
      (node (ref "LD20") (pin "2") (pinfunction "A_2") (pintype "passive"))
      (node (ref "LD21") (pin "2") (pinfunction "A_2") (pintype "passive"))
      (node (ref "R46") (pin "2") (pinfunction "2_2") (pintype "passive"))
    )
    (net (code "74") (name "P5V0") (class "Default")
      (node (ref "C231") (pin "2") (pinfunction "2_2") (pintype "passive"))
      (node (ref "C8") (pin "2") (pinfunction "2_2") (pintype "passive"))
      (node (ref "IC2") (pin "1") (pinfunction "VIN_1") (pintype "input"))
      (node (ref "IC2") (pin "3") (pinfunction "EN_3") (pintype "input"))
      (node (ref "IC7") (pin "1") (pinfunction "VIN_1") (pintype "input"))
      (node (ref "IC7") (pin "3") (pinfunction "EN_3") (pintype "input"))
      (node (ref "J10") (pin "2") (pinfunction "2_2") (pintype "bidirectional"))
      (node (ref "J11") (pin "2") (pinfunction "2_2") (pintype "bidirectional"))
      (node (ref "R47") (pin "2") (pinfunction "2_2") (pintype "passive"))
    )
    (net (code "75") (name "P12V0") (class "Default")
      (node (ref "J10") (pin "1") (pinfunction "1_1") (pintype "bidirectional"))
      (node (ref "J10") (pin "3") (pinfunction "3_3") (pintype "bidirectional"))
      (node (ref "J11") (pin "1") (pinfunction "1_1") (pintype "bidirectional"))
      (node (ref "J11") (pin "3") (pinfunction "3_3") (pintype "bidirectional"))
      (node (ref "R2") (pin "1") (pinfunction "1_1") (pintype "passive"))
    )
    (net (code "76") (name "unconnected-(IC2-NC-Pad4)") (class "Default")
      (node (ref "IC2") (pin "4") (pinfunction "NC_4") (pintype "passive"))
    )
    (net (code "77") (name "unconnected-(IC7-NC-Pad4)") (class "Default")
      (node (ref "IC7") (pin "4") (pinfunction "NC_4") (pintype "passive"))
    )
    (net (code "78") (name "unconnected-(J1-Pad6)") (class "Default")
      (node (ref "J1") (pin "6") (pinfunction "6_6") (pintype "bidirectional"))
    )
    (net (code "79") (name "unconnected-(J1-Pad7)") (class "Default")
      (node (ref "J1") (pin "7") (pinfunction "7_7") (pintype "bidirectional"))
    )
    (net (code "80") (name "unconnected-(J1-Pad8)") (class "Default")
      (node (ref "J1") (pin "8") (pinfunction "8_8") (pintype "bidirectional"))
    )
  )
)
